# ChargeModule.net
KiCad netlist of a schematic drawn in EAGLE
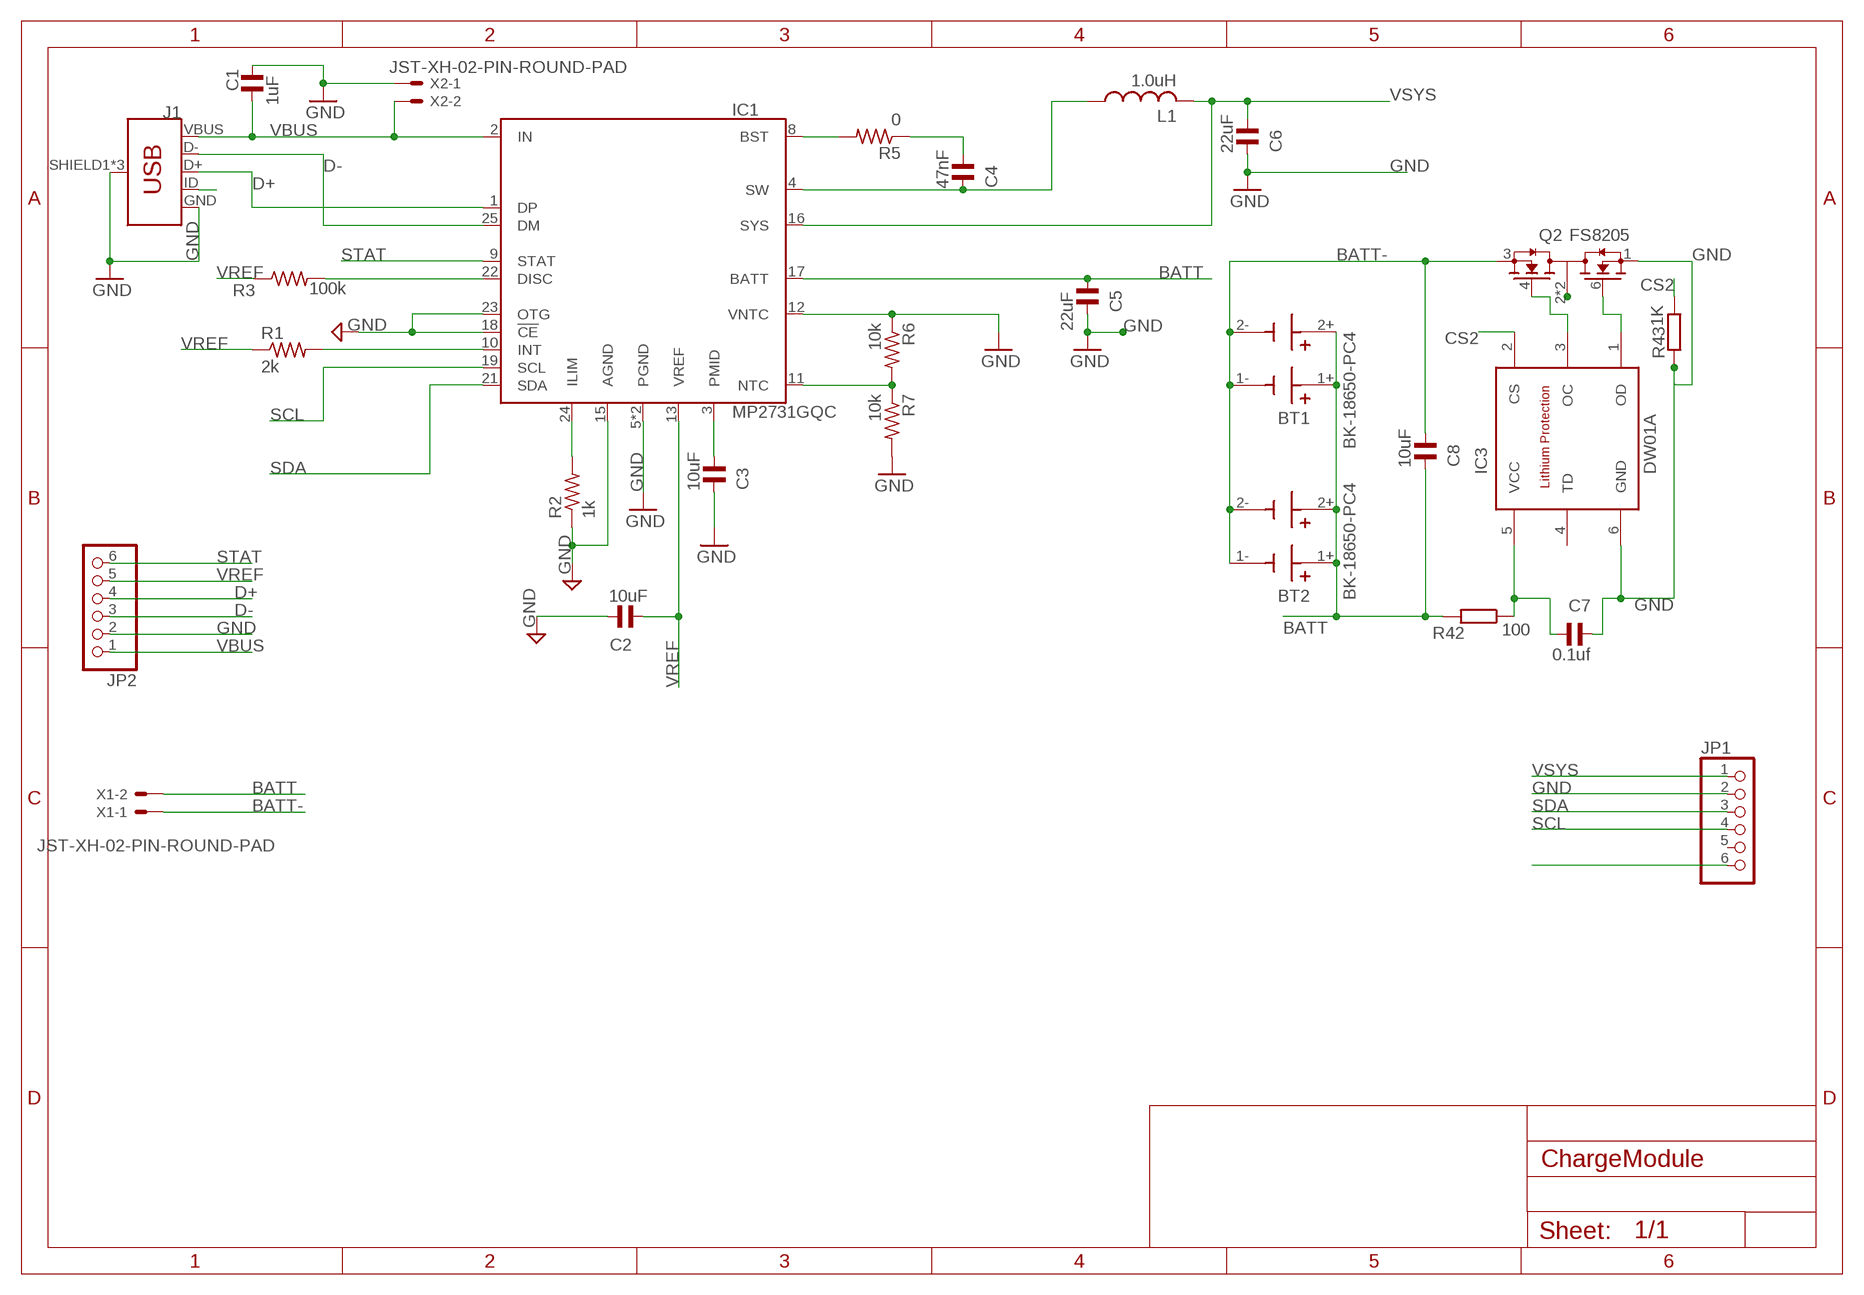
[diagram p0: schematic, sheet 1]

(export (version "E")
  (design (tool "Eeschema 10.0.6"))
  (components
    (comp (ref "BT1")
      (value "BK-18650-PC4")
      (footprint "eagle-import:BAT_BK-18650-PC4")
      (fields (field (name "MF") "MPD"))
      (libsource (lib "eagle-import") (part "BK-18650-PC4"))
    )
    (comp (ref "BT2")
      (value "BK-18650-PC4")
      (footprint "eagle-import:BAT_BK-18650-PC4")
      (fields (field (name "MF") "MPD"))
      (libsource (lib "eagle-import") (part "BK-18650-PC4"))
    )
    (comp (ref "C1")
      (value "1uF")
      (footprint "eagle-import:RC-MASTER-SMD_C0805MP")
      (libsource (lib "eagle-import") (part "RC-MASTER-SMD_C_0805MP"))
    )
    (comp (ref "C2")
      (value "10uF")
      (footprint "eagle-import:RC-MASTER-SMD_C0805MP")
      (libsource (lib "eagle-import") (part "RC-MASTER-SMD_C_0805MP"))
    )
    (comp (ref "C3")
      (value "10uF")
      (footprint "eagle-import:RC-MASTER-SMD_C0805MP")
      (libsource (lib "eagle-import") (part "RC-MASTER-SMD_C_0805MP"))
    )
    (comp (ref "C4")
      (value "47nF")
      (footprint "eagle-import:RC-MASTER-SMD_C0805MP")
      (libsource (lib "eagle-import") (part "RC-MASTER-SMD_C_0805MP"))
    )
    (comp (ref "C5")
      (value "22uF")
      (footprint "eagle-import:RC-MASTER-SMD_C0805MP")
      (libsource (lib "eagle-import") (part "RC-MASTER-SMD_C_0805MP"))
    )
    (comp (ref "C6")
      (value "22uF")
      (footprint "eagle-import:RC-MASTER-SMD_C0805MP")
      (libsource (lib "eagle-import") (part "RC-MASTER-SMD_C_0805MP"))
    )
    (comp (ref "C7")
      (value "0.1uf")
      (footprint "eagle-import:RC-MASTER-SMD_C0805MP")
      (libsource (lib "eagle-import") (part "RC-MASTER-SMD_C_0805MP"))
    )
    (comp (ref "C8")
      (value "10uF")
      (footprint "eagle-import:RC-MASTER-SMD_C0805MP")
      (libsource (lib "eagle-import") (part "RC-MASTER-SMD_C_0805MP"))
    )
    (comp (ref "IC1")
      (value "MP2731GQC")
      (footprint "eagle-import:QFN-26-3.5")
      (fields (field (name "MF") "Monolithic Power") (field (name "MPN") "MP2731GQC-0000-Z"))
      (libsource (lib "eagle-import") (part "MP2731GQC"))
    )
    (comp (ref "IC3")
      (value "DW01A")
      (footprint "eagle-import:SOT23-6")
      (fields (field (name "MF") "Fortune Semiconductor"))
      (libsource (lib "eagle-import") (part "DW01A"))
    )
    (comp (ref "J1")
      (value "USB_MICRO-B_FEMALE-SMT")
      (footprint "eagle-import:USB-B-MICRO-SMD")
      (libsource (lib "eagle-import") (part "USB_MICRO-B_FEMALE-SMT"))
    )
    (comp (ref "JP1")
      (value "PINHD-1X6JSTXH")
      (footprint "eagle-import:JST-XH-06-PACKAGE-ROUND-PAD")
      (libsource (lib "eagle-import") (part "PINHD-1X6JSTXH"))
    )
    (comp (ref "JP2")
      (value "PINHD-1X6JSTXH")
      (footprint "eagle-import:JST-XH-06-PACKAGE-ROUND-PAD")
      (libsource (lib "eagle-import") (part "PINHD-1X6JSTXH"))
    )
    (comp (ref "L1")
      (value "1.0uH")
      (footprint "eagle-import:POWER-CHOKE_WE-TPC")
      (libsource (lib "eagle-import") (part "L-USWE-TPC"))
    )
    (comp (ref "Q2")
      (value "FS8205")
      (footprint "eagle-import:SOT95P280X145-6N")
      (fields (field (name "MF") "Fortune Semiconductor"))
      (libsource (lib "eagle-import") (part "FS8205"))
    )
    (comp (ref "R1")
      (value "2k")
      (footprint "eagle-import:M0805")
      (libsource (lib "eagle-import") (part "R-US_M0805"))
    )
    (comp (ref "R2")
      (value "1k")
      (footprint "eagle-import:M0805")
      (libsource (lib "eagle-import") (part "R-US_M0805"))
    )
    (comp (ref "R3")
      (value "100k")
      (footprint "eagle-import:M0805")
      (libsource (lib "eagle-import") (part "R-US_M0805"))
    )
    (comp (ref "R5")
      (value "0")
      (footprint "eagle-import:M0805")
      (libsource (lib "eagle-import") (part "R-US_M0805"))
    )
    (comp (ref "R6")
      (value "10k")
      (footprint "eagle-import:M0805")
      (libsource (lib "eagle-import") (part "R-US_M0805"))
    )
    (comp (ref "R7")
      (value "10k")
      (footprint "eagle-import:M0805")
      (libsource (lib "eagle-import") (part "R-US_M0805"))
    )
    (comp (ref "R42")
      (value "100")
      (footprint "eagle-import:R0805")
      (libsource (lib "eagle-import") (part "R-EU_R0805"))
    )
    (comp (ref "R43")
      (value "1K")
      (footprint "eagle-import:R0805")
      (libsource (lib "eagle-import") (part "R-EU_R0805"))
    )
    (comp (ref "X1")
      (value "JST-XH-02-PIN-ROUND-PAD")
      (footprint "eagle-import:JST-XH-02-PACKAGE-ROUND-PAD")
      (libsource (lib "eagle-import") (part "JST-XH-02-PIN-ROUND-PAD"))
    )
    (comp (ref "X2")
      (value "JST-XH-02-PIN-ROUND-PAD")
      (footprint "eagle-import:JST-XH-02-PACKAGE-ROUND-PAD")
      (libsource (lib "eagle-import") (part "JST-XH-02-PIN-ROUND-PAD"))
    )
  )
  (nets
    (net (code "1") (name "/BATT") (class "Default")
      (node (ref "BT1") (pin "1+") (pinfunction "1+_1+") (pintype "passive"))
      (node (ref "BT1") (pin "2+") (pinfunction "2+_2+") (pintype "passive"))
      (node (ref "BT2") (pin "1+") (pinfunction "1+_1+") (pintype "passive"))
      (node (ref "BT2") (pin "2+") (pinfunction "2+_2+") (pintype "passive"))
      (node (ref "C5") (pin "1") (pinfunction "1_1") (pintype "passive"))
      (node (ref "C8") (pin "2") (pinfunction "2_2") (pintype "passive"))
      (node (ref "IC1") (pin "17") (pinfunction "BATT_17") (pintype "bidirectional"))
      (node (ref "R42") (pin "2") (pinfunction "2_2") (pintype "passive"))
      (node (ref "X1") (pin "2") (pinfunction "S_2") (pintype "passive"))
    )
    (net (code "2") (name "/BATT-") (class "Default")
      (node (ref "BT1") (pin "1-") (pinfunction "1-_1-") (pintype "passive"))
      (node (ref "BT1") (pin "2-") (pinfunction "2-_2-") (pintype "passive"))
      (node (ref "BT2") (pin "1-") (pinfunction "1-_1-") (pintype "passive"))
      (node (ref "BT2") (pin "2-") (pinfunction "2-_2-") (pintype "passive"))
      (node (ref "C8") (pin "1") (pinfunction "1_1") (pintype "passive"))
      (node (ref "Q2") (pin "3") (pinfunction "S2_3") (pintype "passive"))
      (node (ref "X1") (pin "1") (pinfunction "S_1") (pintype "passive"))
    )
    (net (code "3") (name "/CS2") (class "Default")
      (node (ref "IC3") (pin "2") (pinfunction "CS_2") (pintype "bidirectional"))
      (node (ref "R43") (pin "1") (pinfunction "1_1") (pintype "passive"))
    )
    (net (code "4") (name "/D+") (class "Default")
      (node (ref "IC1") (pin "1") (pinfunction "DP_1") (pintype "bidirectional"))
      (node (ref "J1") (pin "D+") (pinfunction "D+_D+") (pintype "bidirectional"))
      (node (ref "JP2") (pin "4") (pinfunction "4_4") (pintype "passive"))
    )
    (net (code "5") (name "/D-") (class "Default")
      (node (ref "IC1") (pin "25") (pinfunction "DM_25") (pintype "bidirectional"))
      (node (ref "J1") (pin "D-") (pinfunction "D-_D-") (pintype "bidirectional"))
      (node (ref "JP2") (pin "3") (pinfunction "3_3") (pintype "passive"))
    )
    (net (code "6") (name "/SCL") (class "Default")
      (node (ref "IC1") (pin "19") (pinfunction "SCL_19") (pintype "open_collector"))
      (node (ref "JP1") (pin "4") (pinfunction "4_4") (pintype "passive"))
    )
    (net (code "7") (name "/SDA") (class "Default")
      (node (ref "IC1") (pin "21") (pinfunction "SDA_21") (pintype "open_collector"))
      (node (ref "JP1") (pin "3") (pinfunction "3_3") (pintype "passive"))
    )
    (net (code "8") (name "/STAT") (class "Default")
      (node (ref "IC1") (pin "9") (pinfunction "STAT_9") (pintype "open_collector"))
      (node (ref "JP2") (pin "6") (pinfunction "6_6") (pintype "passive"))
    )
    (net (code "9") (name "/VBUS") (class "Default")
      (node (ref "C1") (pin "1") (pinfunction "1_1") (pintype "passive"))
      (node (ref "IC1") (pin "2") (pinfunction "IN_2") (pintype "input"))
      (node (ref "J1") (pin "VBUS") (pinfunction "VBUS_VBUS") (pintype "power_in"))
      (node (ref "JP2") (pin "1") (pinfunction "1_1") (pintype "passive"))
      (node (ref "X2") (pin "2") (pinfunction "S_2") (pintype "passive"))
    )
    (net (code "10") (name "/VREF") (class "Default")
      (node (ref "C2") (pin "1") (pinfunction "1_1") (pintype "passive"))
      (node (ref "IC1") (pin "13") (pinfunction "VREF_13") (pintype "bidirectional"))
      (node (ref "JP2") (pin "5") (pinfunction "5_5") (pintype "passive"))
      (node (ref "R1") (pin "1") (pinfunction "1_1") (pintype "passive"))
      (node (ref "R3") (pin "1") (pinfunction "1_1") (pintype "passive"))
    )
    (net (code "11") (name "/VSYS") (class "Default")
      (node (ref "C6") (pin "1") (pinfunction "1_1") (pintype "passive"))
      (node (ref "IC1") (pin "16") (pinfunction "SYS_16") (pintype "input"))
      (node (ref "JP1") (pin "1") (pinfunction "1_1") (pintype "passive"))
      (node (ref "L1") (pin "2") (pinfunction "2_2") (pintype "passive"))
    )
    (net (code "12") (name "GND") (class "Default")
      (node (ref "C1") (pin "2") (pinfunction "2_2") (pintype "passive"))
      (node (ref "C2") (pin "2") (pinfunction "2_2") (pintype "passive"))
      (node (ref "C3") (pin "2") (pinfunction "2_2") (pintype "passive"))
      (node (ref "C5") (pin "2") (pinfunction "2_2") (pintype "passive"))
      (node (ref "C6") (pin "2") (pinfunction "2_2") (pintype "passive"))
      (node (ref "C7") (pin "2") (pinfunction "2_2") (pintype "passive"))
      (node (ref "IC1") (pin "12") (pinfunction "VNTC_12") (pintype "output"))
      (node (ref "IC1") (pin "15") (pinfunction "AGND_15") (pintype "power_in"))
      (node (ref "IC1") (pin "18") (pinfunction "~{CE}_18") (pintype "input"))
      (node (ref "IC1") (pin "23") (pinfunction "OTG_23") (pintype "input"))
      (node (ref "IC1") (pin "5") (pinfunction "PGND_5") (pintype "power_in"))
      (node (ref "IC1") (pin "6") (pinfunction "PGND_6") (pintype "power_in"))
      (node (ref "IC3") (pin "6") (pinfunction "GND_6") (pintype "power_in"))
      (node (ref "J1") (pin "GND") (pinfunction "GND_GND") (pintype "power_in"))
      (node (ref "J1") (pin "SHIELD1") (pinfunction "SHIELD_SHIELD1") (pintype "bidirectional"))
      (node (ref "J1") (pin "SHIELD2") (pinfunction "SHIELD_SHIELD2") (pintype "bidirectional"))
      (node (ref "J1") (pin "SHIELD3") (pinfunction "SHIELD_SHIELD3") (pintype "bidirectional"))
      (node (ref "JP1") (pin "2") (pinfunction "2_2") (pintype "passive"))
      (node (ref "JP2") (pin "2") (pinfunction "2_2") (pintype "passive"))
      (node (ref "Q2") (pin "1") (pinfunction "S1_1") (pintype "passive"))
      (node (ref "R2") (pin "1") (pinfunction "1_1") (pintype "passive"))
      (node (ref "R43") (pin "2") (pinfunction "2_2") (pintype "passive"))
      (node (ref "R6") (pin "1") (pinfunction "1_1") (pintype "passive"))
      (node (ref "R7") (pin "2") (pinfunction "2_2") (pintype "passive"))
      (node (ref "X2") (pin "1") (pinfunction "S_1") (pintype "passive"))
    )
    (net (code "13") (name "Net-(C4-Pad1)") (class "Default")
      (node (ref "C4") (pin "1") (pinfunction "1_1") (pintype "passive"))
      (node (ref "R5") (pin "1") (pinfunction "1_1") (pintype "passive"))
    )
    (net (code "14") (name "Net-(IC1-BST)") (class "Default")
      (node (ref "IC1") (pin "8") (pinfunction "BST_8") (pintype "bidirectional"))
      (node (ref "R5") (pin "2") (pinfunction "2_2") (pintype "passive"))
    )
    (net (code "15") (name "Net-(IC1-DISC)") (class "Default")
      (node (ref "IC1") (pin "22") (pinfunction "DISC_22") (pintype "input"))
      (node (ref "R3") (pin "2") (pinfunction "2_2") (pintype "passive"))
    )
    (net (code "16") (name "Net-(IC1-ILIM)") (class "Default")
      (node (ref "IC1") (pin "24") (pinfunction "ILIM_24") (pintype "bidirectional"))
      (node (ref "R2") (pin "2") (pinfunction "2_2") (pintype "passive"))
    )
    (net (code "17") (name "Net-(IC1-INT)") (class "Default")
      (node (ref "IC1") (pin "10") (pinfunction "INT_10") (pintype "open_collector"))
      (node (ref "R1") (pin "2") (pinfunction "2_2") (pintype "passive"))
    )
    (net (code "18") (name "Net-(IC1-NTC)") (class "Default")
      (node (ref "IC1") (pin "11") (pinfunction "NTC_11") (pintype "input"))
      (node (ref "R6") (pin "2") (pinfunction "2_2") (pintype "passive"))
      (node (ref "R7") (pin "1") (pinfunction "1_1") (pintype "passive"))
    )
    (net (code "19") (name "Net-(IC1-PMID)") (class "Default")
      (node (ref "C3") (pin "1") (pinfunction "1_1") (pintype "passive"))
      (node (ref "IC1") (pin "3") (pinfunction "PMID_3") (pintype "bidirectional"))
    )
    (net (code "20") (name "Net-(IC1-SW)") (class "Default")
      (node (ref "C4") (pin "2") (pinfunction "2_2") (pintype "passive"))
      (node (ref "IC1") (pin "4") (pinfunction "SW_4") (pintype "output"))
      (node (ref "L1") (pin "1") (pinfunction "1_1") (pintype "passive"))
    )
    (net (code "21") (name "Net-(IC3-OC)") (class "Default")
      (node (ref "IC3") (pin "3") (pinfunction "OC_3") (pintype "bidirectional"))
      (node (ref "Q2") (pin "4") (pinfunction "G2_4") (pintype "passive"))
    )
    (net (code "22") (name "Net-(IC3-OD)") (class "Default")
      (node (ref "IC3") (pin "1") (pinfunction "OD_1") (pintype "bidirectional"))
      (node (ref "Q2") (pin "6") (pinfunction "G1_6") (pintype "passive"))
    )
    (net (code "23") (name "Net-(IC3-VCC)") (class "Default")
      (node (ref "C7") (pin "1") (pinfunction "1_1") (pintype "passive"))
      (node (ref "IC3") (pin "5") (pinfunction "VCC_5") (pintype "power_in"))
      (node (ref "R42") (pin "1") (pinfunction "1_1") (pintype "passive"))
    )
    (net (code "24") (name "Net-(Q2-D12-Pad2)") (class "Default")
      (node (ref "Q2") (pin "2") (pinfunction "D12_2") (pintype "passive"))
      (node (ref "Q2") (pin "5") (pinfunction "D12_5") (pintype "passive"))
    )
    (net (code "25") (name "unconnected-(IC3-TD-Pad4)") (class "Default")
      (node (ref "IC3") (pin "4") (pinfunction "TD_4") (pintype "bidirectional"))
    )
    (net (code "26") (name "unconnected-(J1-PadID)") (class "Default")
      (node (ref "J1") (pin "ID") (pinfunction "ID_ID") (pintype "bidirectional"))
    )
    (net (code "27") (name "unconnected-(JP1-Pad5)") (class "Default")
      (node (ref "JP1") (pin "5") (pinfunction "5_5") (pintype "passive"))
    )
    (net (code "28") (name "unconnected-(JP1-Pad6)") (class "Default")
      (node (ref "JP1") (pin "6") (pinfunction "6_6") (pintype "passive"))
    )
  )
)
